# 09_ETHERNET_ENET.net
KiCad netlist of a schematic drawn in Altium Designer
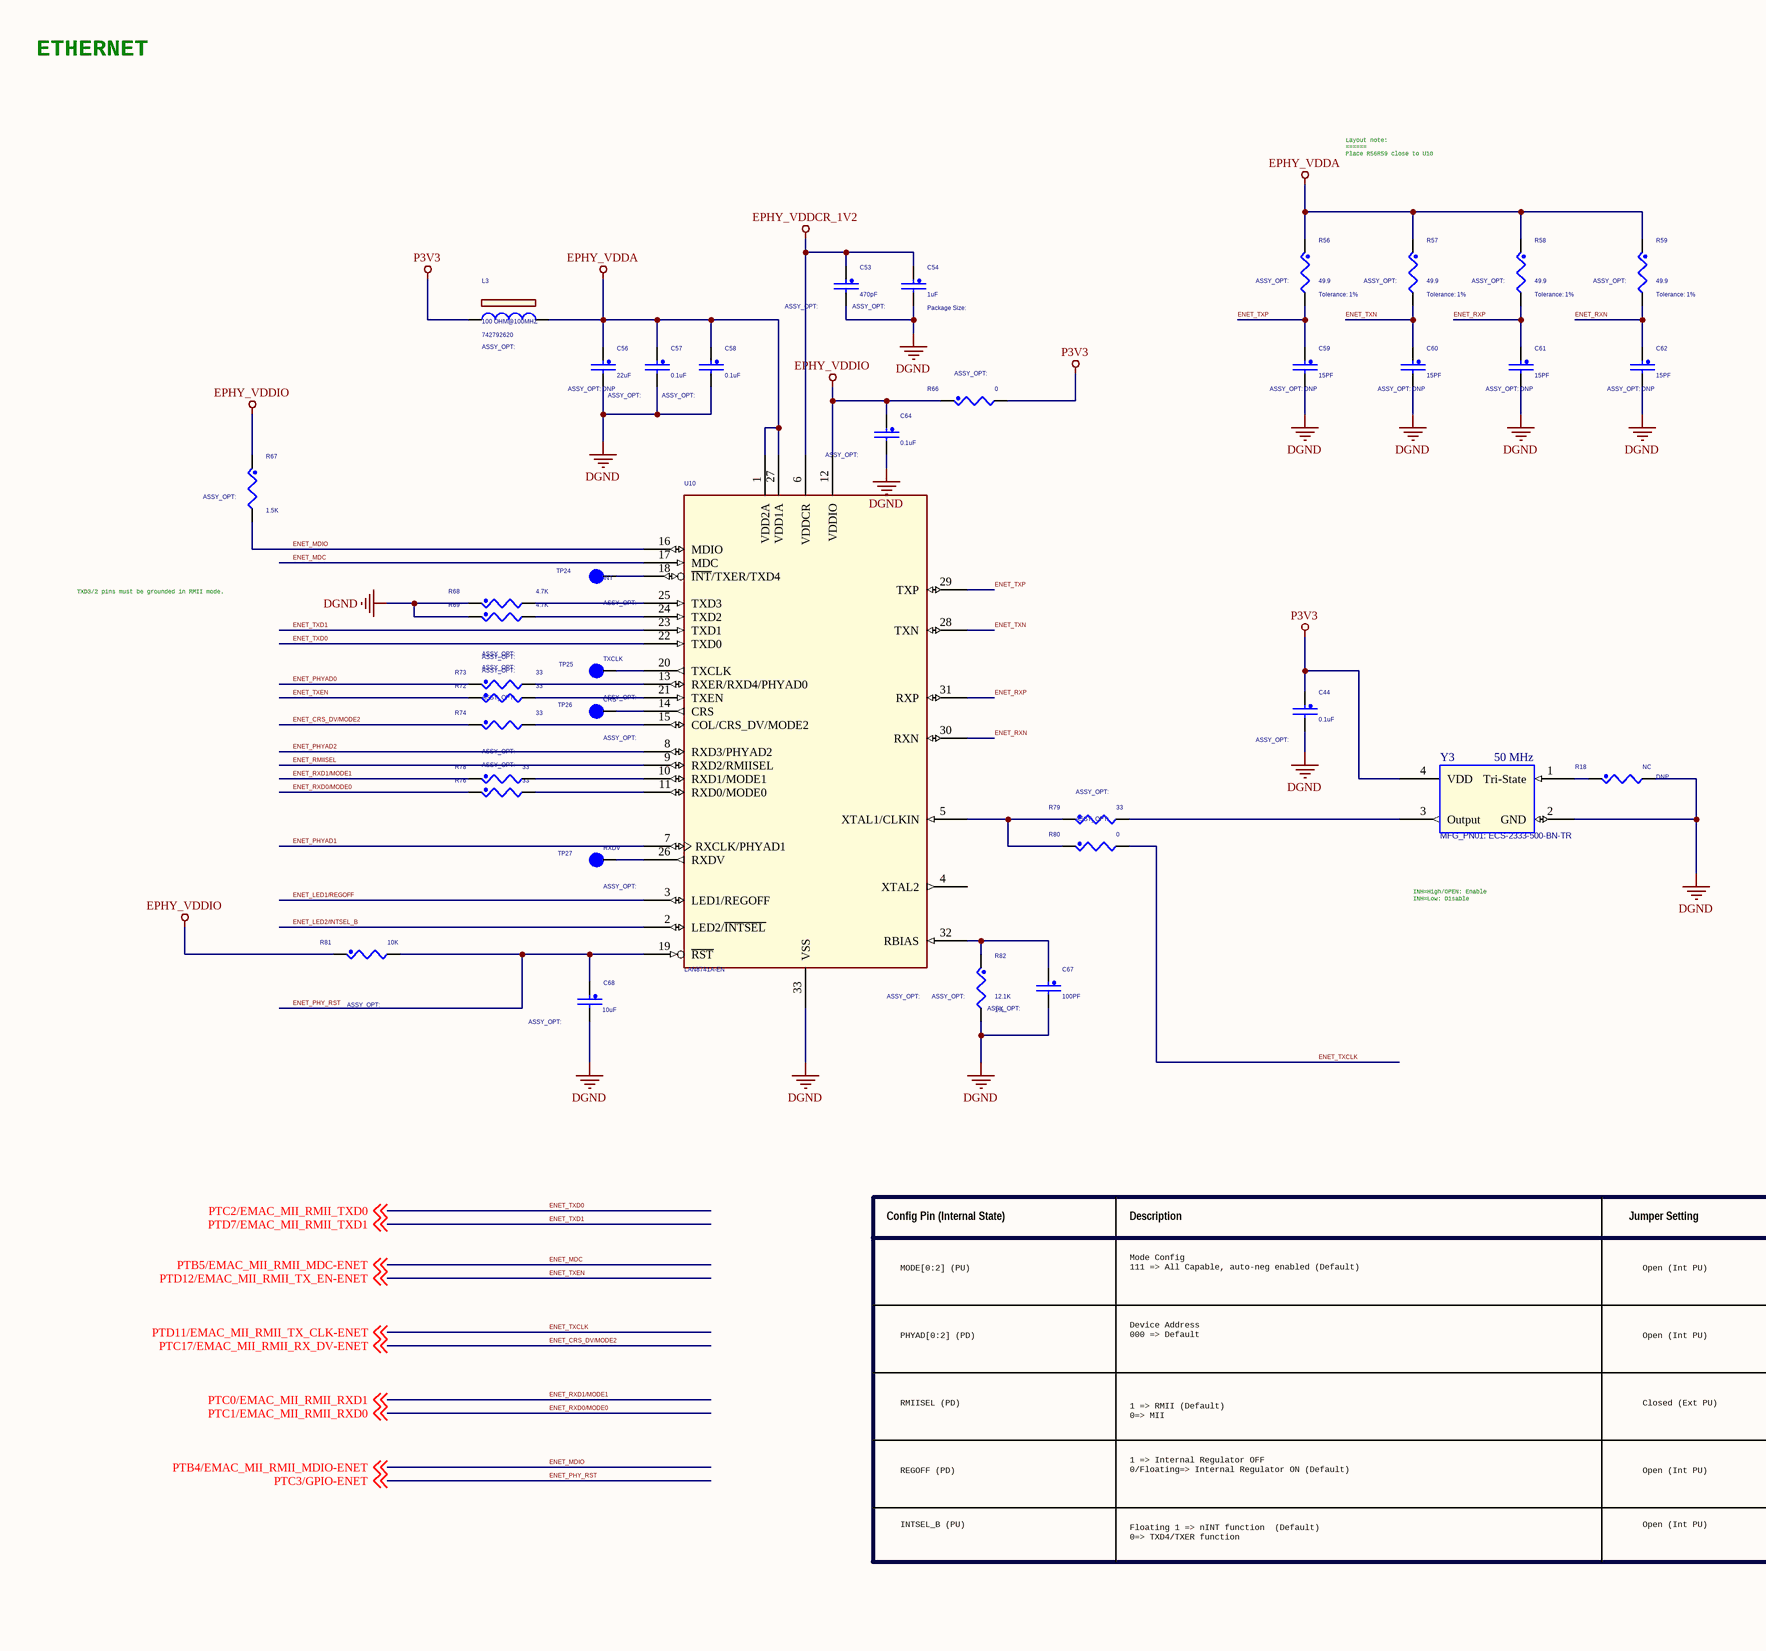
[diagram p0: 09 ETHERNET_ENET.SchDoc, left]
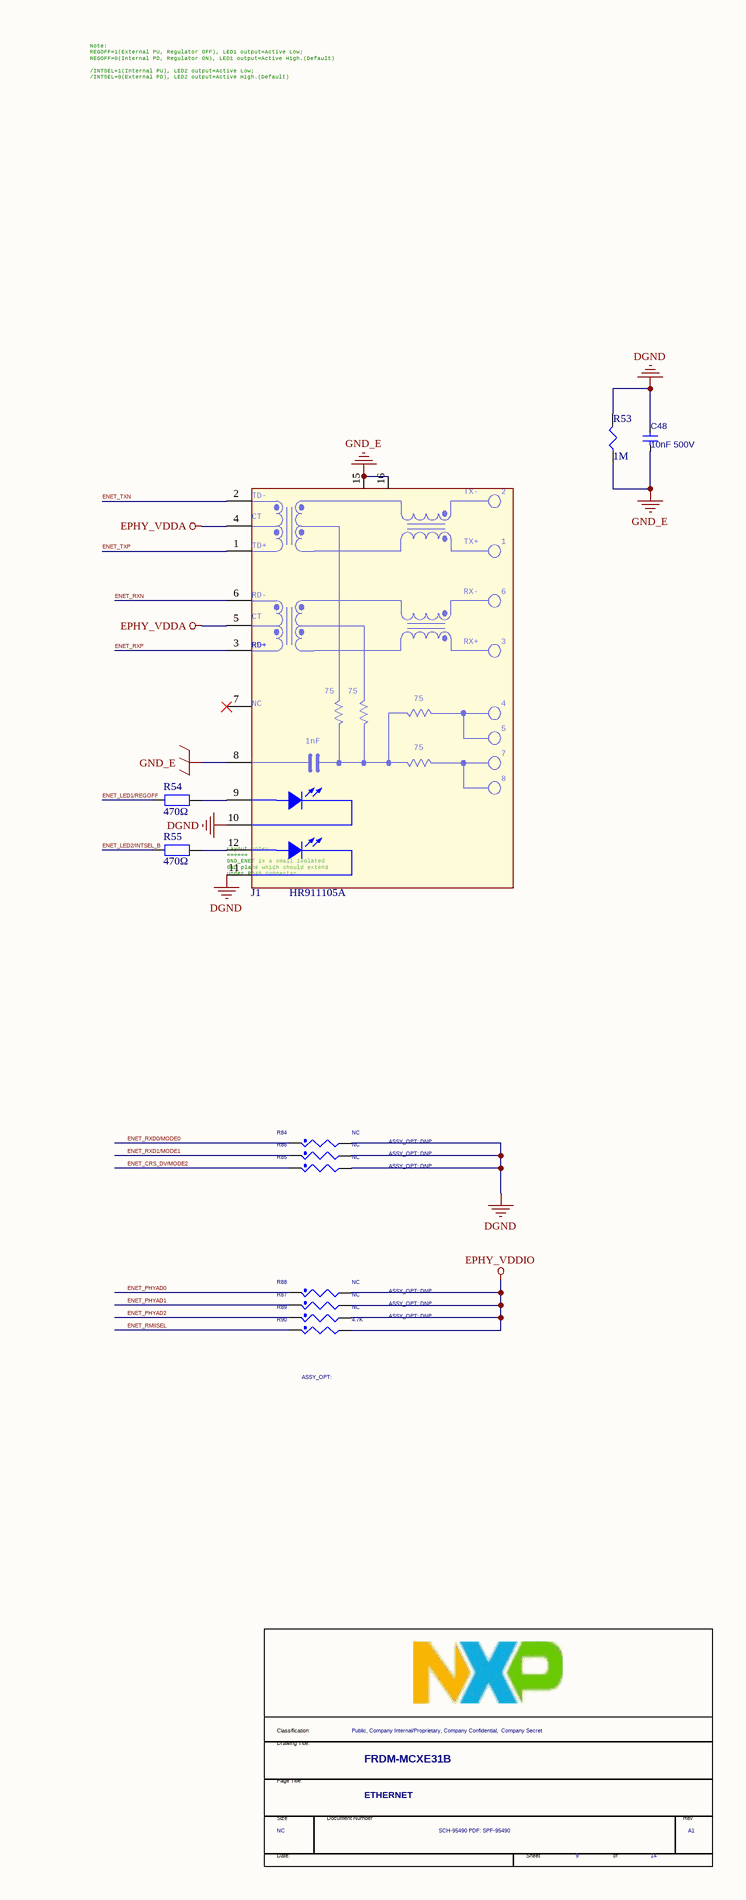
[diagram p1: 09 ETHERNET_ENET.SchDoc, right]

(export (version "E")
  (design (tool "Eeschema 10.0.6"))
  (components
    (comp (ref "C44")
      (value "0.1uF")
      (footprint "CC0402_25")
      (description "CAP CER 0.1UF 16V 10% X7R 0402")
      (fields (field (name "TOLERANCE") "10%") (field (name "VOLTAGE") "16V"))
      (libsource (lib "*") (part "CAP_NP"))
    )
    (comp (ref "C48") (value "10nF 500V") (footprint "1210") (libsource (lib "*") (part "CAP")))
    (comp (ref "C53")
      (value "470pF")
      (footprint "CC0402_25")
      (description "CAP CER 470pF 50V 5% C0G 0402")
      (fields (field (name "TOLERANCE") "5%"))
      (libsource (lib "*") (part "CAP_NP"))
    )
    (comp (ref "C54")
      (value "1uF")
      (footprint "CC0402_25")
      (description "CAP CER 1.0uF 16V 10% X6S 0402")
      (fields (field (name "VOLTAGE") "16V") (field (name "TOLERANCE") "10%"))
      (libsource (lib "*") (part "CAP_NP"))
    )
    (comp (ref "C56")
      (value "22uF")
      (footprint "CC0603_OV")
      (description "CAP CER 22uF 10V 20% X5R 0603")
      (fields (field (name "ASSY_OPT") "DNP") (field (name "TOLERANCE") "20%"))
      (libsource (lib "*") (part "CAP_NP"))
    )
    (comp (ref "C57")
      (value "0.1uF")
      (footprint "CC0402_25")
      (description "CAP CER 0.1UF 16V 10% X7R 0402")
      (fields (field (name "TOLERANCE") "10%") (field (name "VOLTAGE") "16V"))
      (libsource (lib "*") (part "CAP_NP"))
    )
    (comp (ref "C58")
      (value "0.1uF")
      (footprint "CC0402_25")
      (description "CAP CER 0.1UF 16V 10% X7R 0402")
      (fields (field (name "TOLERANCE") "10%") (field (name "VOLTAGE") "16V"))
      (libsource (lib "*") (part "CAP_NP"))
    )
    (comp (ref "C59")
      (value "15PF")
      (footprint "CC0402_25")
      (description "CAP CER 15pF 50V 5% C0G 0402")
      (fields (field (name "ASSY_OPT") "DNP") (field (name "TOLERANCE") "5%"))
      (libsource (lib "*") (part "CAP_NP"))
    )
    (comp (ref "C60")
      (value "15PF")
      (footprint "CC0402_25")
      (description "CAP CER 15pF 50V 5% C0G 0402")
      (fields (field (name "ASSY_OPT") "DNP") (field (name "TOLERANCE") "5%"))
      (libsource (lib "*") (part "CAP_NP"))
    )
    (comp (ref "C61")
      (value "15PF")
      (footprint "CC0402_25")
      (description "CAP CER 15pF 50V 5% C0G 0402")
      (fields (field (name "ASSY_OPT") "DNP") (field (name "TOLERANCE") "5%"))
      (libsource (lib "*") (part "CAP_NP"))
    )
    (comp (ref "C62")
      (value "15PF")
      (footprint "CC0402_25")
      (description "CAP CER 15pF 50V 5% C0G 0402")
      (fields (field (name "ASSY_OPT") "DNP") (field (name "TOLERANCE") "5%"))
      (libsource (lib "*") (part "CAP_NP"))
    )
    (comp (ref "C64")
      (value "0.1uF")
      (footprint "CC0402_25")
      (description "CAP CER 0.1UF 16V 10% X7R 0402")
      (fields (field (name "TOLERANCE") "10%") (field (name "VOLTAGE") "16V"))
      (libsource (lib "*") (part "CAP_NP"))
    )
    (comp (ref "C67")
      (value "100PF")
      (footprint "CC0402_25")
      (description "CAP CER 100pF 16V 10% X7R 0402")
      (fields (field (name "TOLERANCE") "10%"))
      (libsource (lib "*") (part "CAP_NP"))
    )
    (comp (ref "C68")
      (value "10uF")
      (footprint "CC0402_25")
      (description "CAP CER 10uF 25V 20% X5R 0603")
      (fields (field (name "TOLERANCE") "20%"))
      (libsource (lib "*") (part "CAP_NP"))
    )
    (comp (ref "J1")
      (value "HR911105A")
      (footprint "RJ45-HR911105A")
      (libsource (lib "GatewaySchlib_V2") (part "HR911105A"))
    )
    (comp (ref "L3")
      (value "100 OHM@100MHZ")
      (footprint "L 0603_L")
      (description "IND FER BEAD 100 OHM@100MHz 0.5A 25% AEC-Q200 0603")
      (fields (field (name "MFG_PN01") "742792620"))
      (libsource (lib "*") (part "INDUCTOR_FERRITE"))
    )
    (comp (ref "R18")
      (value "NC")
      (footprint "RC0402_25")
      (description "RES MF ZERO OHM 1/10W -- 0603")
      (fields (field (name "ASSY_OPT") "DNP"))
      (libsource (lib "*") (part "RES"))
    )
    (comp (ref "R53") (value "1M") (footprint "1210") (libsource (lib "armdesign_schlib1") (part "R")))
    (comp (ref "R54")
      (value "470Ω")
      (footprint "R0603")
      (description "贴片电阻")
      (fields (field (name "版权归属") "源创客"))
      (libsource (lib "PCB_Project_1") (part "R"))
    )
    (comp (ref "R55")
      (value "470Ω")
      (footprint "R0603")
      (description "贴片电阻")
      (fields (field (name "版权归属") "源创客"))
      (libsource (lib "PCB_Project_1") (part "R"))
    )
    (comp (ref "R56")
      (value "49.9")
      (footprint "RC0402_25")
      (description "RES MF 49.9 OHM 1/16W 1% 0402")
      (fields (field (name "TOLERANCE") "1%"))
      (libsource (lib "*") (part "RES"))
    )
    (comp (ref "R57")
      (value "49.9")
      (footprint "RC0402_25")
      (description "RES MF 49.9 OHM 1/16W 1% 0402")
      (fields (field (name "TOLERANCE") "1%"))
      (libsource (lib "*") (part "RES"))
    )
    (comp (ref "R58")
      (value "49.9")
      (footprint "RC0402_25")
      (description "RES MF 49.9 OHM 1/16W 1% 0402")
      (fields (field (name "TOLERANCE") "1%"))
      (libsource (lib "*") (part "RES"))
    )
    (comp (ref "R59")
      (value "49.9")
      (footprint "RC0402_25")
      (description "RES MF 49.9 OHM 1/16W 1% 0402")
      (fields (field (name "TOLERANCE") "1%"))
      (libsource (lib "*") (part "RES"))
    )
    (comp (ref "R66")
      (value "0")
      (footprint "RC0603_OV")
      (description "RES MF ZERO OHM 1/10W -- 0603")
      (libsource (lib "*") (part "RES"))
    )
    (comp (ref "R67")
      (value "1.5K")
      (footprint "RC0402_25")
      (description "RES MF 1.5K 1/16W 1% 0402")
      (fields (field (name "TOLERANCE") "1%"))
      (libsource (lib "*") (part "RES"))
    )
    (comp (ref "R68")
      (value "4.7K")
      (footprint "RC0402_25")
      (description "RES MF 4.7K 1/16W 5% 0402")
      (fields (field (name "TOLERANCE") "5%"))
      (libsource (lib "*") (part "RES"))
    )
    (comp (ref "R69")
      (value "4.7K")
      (footprint "RC0402_25")
      (description "RES MF 4.7K 1/16W 5% 0402")
      (fields (field (name "TOLERANCE") "5%"))
      (libsource (lib "*") (part "RES"))
    )
    (comp (ref "R72")
      (value "33")
      (footprint "RC0402_25")
      (description "RES MF 33.0 OHM 1/16W 1% 0402")
      (fields (field (name "TOLERANCE") "1%"))
      (libsource (lib "*") (part "RES"))
    )
    (comp (ref "R73")
      (value "33")
      (footprint "RC0402_25")
      (description "RES MF 33.0 OHM 1/16W 1% 0402")
      (fields (field (name "TOLERANCE") "1%"))
      (libsource (lib "*") (part "RES"))
    )
    (comp (ref "R74")
      (value "33")
      (footprint "RC0402_25")
      (description "RES MF 33.0 OHM 1/16W 1% 0402")
      (fields (field (name "TOLERANCE") "1%"))
      (libsource (lib "*") (part "RES"))
    )
    (comp (ref "R76")
      (value "33")
      (footprint "RC0402_25")
      (description "RES MF 33.0 OHM 1/16W 1% 0402")
      (fields (field (name "TOLERANCE") "1%"))
      (libsource (lib "*") (part "RES"))
    )
    (comp (ref "R78")
      (value "33")
      (footprint "RC0402_25")
      (description "RES MF 33.0 OHM 1/16W 1% 0402")
      (fields (field (name "TOLERANCE") "1%"))
      (libsource (lib "*") (part "RES"))
    )
    (comp (ref "R79")
      (value "33")
      (footprint "RC0402_25")
      (description "RES MF 33.0 OHM 1/16W 1% 0402")
      (fields (field (name "TOLERANCE") "1%"))
      (libsource (lib "*") (part "RES"))
    )
    (comp (ref "R80")
      (value "0")
      (footprint "RC0402_25")
      (description "RES MF ZERO OHM 1/10W -- 0603")
      (libsource (lib "*") (part "RES"))
    )
    (comp (ref "R81")
      (value "10K")
      (footprint "RC0402_25")
      (description "RES MF 10K 1/16W 5% 0402")
      (fields (field (name "TOLERANCE") "5%"))
      (libsource (lib "*") (part "RES"))
    )
    (comp (ref "R82")
      (value "12.1K")
      (footprint "RC0402_25")
      (description "RES MF 12.1K 1/16W 1% 0402")
      (fields (field (name "TOLERANCE") "1%"))
      (libsource (lib "*") (part "RES"))
    )
    (comp (ref "R84")
      (value "NC")
      (footprint "RC0402_25")
      (description "RES MF 4.7K 1/16W 5% 0402")
      (fields (field (name "ASSY_OPT") "DNP") (field (name "TOLERANCE") "5%"))
      (libsource (lib "*") (part "RES"))
    )
    (comp (ref "R85")
      (value "NC")
      (footprint "RC0402_25")
      (description "RES MF 4.7K 1/16W 5% 0402")
      (fields (field (name "ASSY_OPT") "DNP") (field (name "TOLERANCE") "5%"))
      (libsource (lib "*") (part "RES"))
    )
    (comp (ref "R86")
      (value "NC")
      (footprint "RC0402_25")
      (description "RES MF 4.7K 1/16W 5% 0402")
      (fields (field (name "ASSY_OPT") "DNP") (field (name "TOLERANCE") "5%"))
      (libsource (lib "*") (part "RES"))
    )
    (comp (ref "R87")
      (value "NC")
      (footprint "RC0402_25")
      (description "RES MF 4.7K 1/16W 5% 0402")
      (fields (field (name "ASSY_OPT") "DNP") (field (name "TOLERANCE") "5%"))
      (libsource (lib "*") (part "RES"))
    )
    (comp (ref "R88")
      (value "NC")
      (footprint "RC0402_25")
      (description "RES MF 4.7K 1/16W 5% 0402")
      (fields (field (name "ASSY_OPT") "DNP") (field (name "TOLERANCE") "5%"))
      (libsource (lib "*") (part "RES"))
    )
    (comp (ref "R89")
      (value "NC")
      (footprint "RC0402_25")
      (description "RES MF 4.7K 1/16W 5% 0402")
      (fields (field (name "ASSY_OPT") "DNP") (field (name "TOLERANCE") "5%"))
      (libsource (lib "*") (part "RES"))
    )
    (comp (ref "R90")
      (value "4.7K")
      (footprint "RC0402_25")
      (description "RES MF 4.7K 1/16W 5% 0402")
      (fields (field (name "TOLERANCE") "5%"))
      (libsource (lib "*") (part "RES"))
    )
    (comp (ref "TP24")
      (value "TPAD_030")
      (footprint "TPAD_030")
      (description "TEST POINT PAD 30MIL DIA SMT, NO PART TO ORDER")
      (fields (field (name "SILK") "INT"))
      (libsource (lib "*") (part "TESTLOOP"))
    )
    (comp (ref "TP25")
      (value "TPAD_030")
      (footprint "TPAD_030")
      (description "TEST POINT PAD 30MIL DIA SMT, NO PART TO ORDER")
      (fields (field (name "SILK") "TXCLK"))
      (libsource (lib "*") (part "TESTLOOP"))
    )
    (comp (ref "TP26")
      (value "TPAD_030")
      (footprint "TPAD_030")
      (description "TEST POINT PAD 30MIL DIA SMT, NO PART TO ORDER")
      (fields (field (name "SILK") "CRS"))
      (libsource (lib "*") (part "TESTLOOP"))
    )
    (comp (ref "TP27")
      (value "TPAD_030")
      (footprint "TPAD_030")
      (description "TEST POINT PAD 30MIL DIA SMT, NO PART TO ORDER")
      (fields (field (name "SILK") "RXDV"))
      (libsource (lib "*") (part "TESTLOOP"))
    )
    (comp (ref "U10")
      (value "LAN8741A-EN")
      (footprint "QFN-32-EP(5x5)")
      (description "IC XCVR ETHERNET PHY MII/RMII 1.8-3.3V SQFN32")
      (fields (field (name "MFG_PN01") "LAN8741A-EN"))
      (libsource (lib "*") (part "LAN8710"))
    )
    (comp (ref "Y3")
      (value "50 MHz")
      (footprint "OSC-SMD_4P-L3.2-W2.5-BL")
      (description "OSC XO 50MHZ 3.3V SMD")
      (fields (field (name "MFG_PN01") "ECS-2333-500-BN-TR"))
      (libsource (lib "PCB_Project") (part "OSC_ASFL"))
    )
  )
  (nets
    (net (code "1") (name "/ENET_LED1{slash}REGOFF") (class "Default")
      (node (ref "R54") (pin "2") (pinfunction "2_2") (pintype "passive"))
      (node (ref "U10") (pin "3") (pinfunction "LED1/REGOFF_3") (pintype "bidirectional"))
    )
    (net (code "2") (name "/ENET_LED2{slash}INTSEL_B") (class "Default")
      (node (ref "R55") (pin "2") (pinfunction "2_2") (pintype "passive"))
      (node (ref "U10") (pin "2") (pinfunction "LED2/~{INTSEL}_2") (pintype "bidirectional"))
    )
    (net (code "3") (name "/ENET_PHYAD0") (class "Default")
      (node (ref "R73") (pin "1") (pinfunction "1_1") (pintype "passive"))
      (node (ref "R88") (pin "1") (pinfunction "1_1") (pintype "passive"))
    )
    (net (code "4") (name "/ENET_PHYAD1") (class "Default")
      (node (ref "R87") (pin "1") (pinfunction "1_1") (pintype "passive"))
      (node (ref "U10") (pin "7") (pinfunction "RXCLK/PHYAD1_7") (pintype "bidirectional"))
    )
    (net (code "5") (name "/ENET_PHYAD2") (class "Default")
      (node (ref "R89") (pin "1") (pinfunction "1_1") (pintype "passive"))
      (node (ref "U10") (pin "8") (pinfunction "RXD3/PHYAD2_8") (pintype "bidirectional"))
    )
    (net (code "6") (name "/ENET_RMIISEL") (class "Default")
      (node (ref "R90") (pin "1") (pinfunction "1_1") (pintype "passive"))
      (node (ref "U10") (pin "9") (pinfunction "RXD2/RMIISEL_9") (pintype "bidirectional"))
    )
    (net (code "7") (name "/ENET_RXN") (class "Default")
      (node (ref "C62") (pin "1") (pinfunction "1_1") (pintype "passive"))
      (node (ref "J1") (pin "6") (pinfunction "P6_6") (pintype "passive"))
      (node (ref "R59") (pin "2") (pinfunction "2_2") (pintype "passive"))
      (node (ref "U10") (pin "30") (pinfunction "RXN_30") (pintype "bidirectional"))
    )
    (net (code "8") (name "/ENET_RXP") (class "Default")
      (node (ref "C61") (pin "1") (pinfunction "1_1") (pintype "passive"))
      (node (ref "J1") (pin "3") (pinfunction "P3_3") (pintype "passive"))
      (node (ref "R58") (pin "2") (pinfunction "2_2") (pintype "passive"))
      (node (ref "U10") (pin "31") (pinfunction "RXP_31") (pintype "bidirectional"))
    )
    (net (code "9") (name "/ENET_TXN") (class "Default")
      (node (ref "C60") (pin "1") (pinfunction "1_1") (pintype "passive"))
      (node (ref "J1") (pin "2") (pinfunction "P2_2") (pintype "passive"))
      (node (ref "R57") (pin "2") (pinfunction "2_2") (pintype "passive"))
      (node (ref "U10") (pin "28") (pinfunction "TXN_28") (pintype "bidirectional"))
    )
    (net (code "10") (name "/ENET_TXP") (class "Default")
      (node (ref "C59") (pin "1") (pinfunction "1_1") (pintype "passive"))
      (node (ref "J1") (pin "1") (pinfunction "P1_1") (pintype "passive"))
      (node (ref "R56") (pin "2") (pinfunction "2_2") (pintype "passive"))
      (node (ref "U10") (pin "29") (pinfunction "TXP_29") (pintype "bidirectional"))
    )
    (net (code "11") (name "DGND") (class "Default")
      (node (ref "C44") (pin "2") (pinfunction "2_2") (pintype "passive"))
      (node (ref "C48") (pin "2") (pintype "passive"))
      (node (ref "C53") (pin "2") (pinfunction "2_2") (pintype "passive"))
      (node (ref "C54") (pin "2") (pinfunction "2_2") (pintype "passive"))
      (node (ref "C56") (pin "2") (pinfunction "2_2") (pintype "passive"))
      (node (ref "C57") (pin "2") (pinfunction "2_2") (pintype "passive"))
      (node (ref "C58") (pin "2") (pinfunction "2_2") (pintype "passive"))
      (node (ref "C59") (pin "2") (pinfunction "2_2") (pintype "passive"))
      (node (ref "C60") (pin "2") (pinfunction "2_2") (pintype "passive"))
      (node (ref "C61") (pin "2") (pinfunction "2_2") (pintype "passive"))
      (node (ref "C62") (pin "2") (pinfunction "2_2") (pintype "passive"))
      (node (ref "C64") (pin "2") (pinfunction "2_2") (pintype "passive"))
      (node (ref "C67") (pin "2") (pinfunction "2_2") (pintype "passive"))
      (node (ref "C68") (pin "2") (pinfunction "2_2") (pintype "passive"))
      (node (ref "J1") (pin "10") (pinfunction "CATHODE_10") (pintype "passive"))
      (node (ref "J1") (pin "11") (pinfunction "CATHODE_11") (pintype "passive"))
      (node (ref "R18") (pin "2") (pinfunction "2_2") (pintype "passive"))
      (node (ref "R53") (pin "2") (pinfunction "2_2") (pintype "passive"))
      (node (ref "R68") (pin "1") (pinfunction "1_1") (pintype "passive"))
      (node (ref "R69") (pin "1") (pinfunction "1_1") (pintype "passive"))
      (node (ref "R82") (pin "2") (pinfunction "2_2") (pintype "passive"))
      (node (ref "R84") (pin "2") (pinfunction "2_2") (pintype "passive"))
      (node (ref "R85") (pin "2") (pinfunction "2_2") (pintype "passive"))
      (node (ref "R86") (pin "2") (pinfunction "2_2") (pintype "passive"))
      (node (ref "U10") (pin "33") (pinfunction "VSS_33") (pintype "power_in"))
      (node (ref "Y3") (pin "2") (pinfunction "GND_2") (pintype "bidirectional"))
    )
    (net (code "12") (name "EPHY_VDDA") (class "Default")
      (node (ref "C56") (pin "1") (pinfunction "1_1") (pintype "passive"))
      (node (ref "C57") (pin "1") (pinfunction "1_1") (pintype "passive"))
      (node (ref "C58") (pin "1") (pinfunction "1_1") (pintype "passive"))
      (node (ref "J1") (pin "4") (pinfunction "P4_4") (pintype "passive"))
      (node (ref "J1") (pin "5") (pinfunction "P5_5") (pintype "passive"))
      (node (ref "L3") (pin "2") (pinfunction "2_2") (pintype "passive"))
      (node (ref "R56") (pin "1") (pinfunction "1_1") (pintype "passive"))
      (node (ref "R57") (pin "1") (pinfunction "1_1") (pintype "passive"))
      (node (ref "R58") (pin "1") (pinfunction "1_1") (pintype "passive"))
      (node (ref "R59") (pin "1") (pinfunction "1_1") (pintype "passive"))
      (node (ref "U10") (pin "1") (pinfunction "VDD2A_1") (pintype "power_in"))
      (node (ref "U10") (pin "27") (pinfunction "VDD1A_27") (pintype "power_in"))
    )
    (net (code "13") (name "EPHY_VDDCR_1V2") (class "Default")
      (node (ref "C53") (pin "1") (pinfunction "1_1") (pintype "passive"))
      (node (ref "C54") (pin "1") (pinfunction "1_1") (pintype "passive"))
      (node (ref "U10") (pin "6") (pinfunction "VDDCR_6") (pintype "power_in"))
    )
    (net (code "14") (name "EPHY_VDDIO") (class "Default")
      (node (ref "C64") (pin "1") (pinfunction "1_1") (pintype "passive"))
      (node (ref "R66") (pin "1") (pinfunction "1_1") (pintype "passive"))
      (node (ref "R67") (pin "1") (pinfunction "1_1") (pintype "passive"))
      (node (ref "R81") (pin "1") (pinfunction "1_1") (pintype "passive"))
      (node (ref "R87") (pin "2") (pinfunction "2_2") (pintype "passive"))
      (node (ref "R88") (pin "2") (pinfunction "2_2") (pintype "passive"))
      (node (ref "R89") (pin "2") (pinfunction "2_2") (pintype "passive"))
      (node (ref "R90") (pin "2") (pinfunction "2_2") (pintype "passive"))
      (node (ref "U10") (pin "12") (pinfunction "VDDIO_12") (pintype "power_in"))
    )
    (net (code "15") (name "GND_E") (class "Default")
      (node (ref "C48") (pin "1") (pintype "passive"))
      (node (ref "J1") (pin "15") (pinfunction "P15_15") (pintype "passive"))
      (node (ref "J1") (pin "16") (pinfunction "P16_16") (pintype "passive"))
      (node (ref "J1") (pin "8") (pinfunction "P8_8") (pintype "passive"))
      (node (ref "R53") (pin "1") (pinfunction "1_1") (pintype "passive"))
    )
    (net (code "16") (name "Net-(J1-ANODE-Pad9)") (class "Default")
      (node (ref "J1") (pin "9") (pinfunction "ANODE_9") (pintype "passive"))
      (node (ref "R54") (pin "1") (pinfunction "1_1") (pintype "passive"))
    )
    (net (code "17") (name "Net-(J1-ANODE-Pad12)") (class "Default")
      (node (ref "J1") (pin "12") (pinfunction "ANODE_12") (pintype "passive"))
      (node (ref "R55") (pin "1") (pinfunction "1_1") (pintype "passive"))
    )
    (net (code "18") (name "Net-(TP24-Pin1)") (class "Default")
      (node (ref "TP24") (pin "1") (pinfunction "Pin1_1") (pintype "passive"))
      (node (ref "U10") (pin "18") (pinfunction "~{INT}/TXER/TXD4_18") (pintype "bidirectional"))
    )
    (net (code "19") (name "Net-(TP25-Pin1)") (class "Default")
      (node (ref "TP25") (pin "1") (pinfunction "Pin1_1") (pintype "passive"))
      (node (ref "U10") (pin "20") (pinfunction "TXCLK_20") (pintype "output"))
    )
    (net (code "20") (name "Net-(TP26-Pin1)") (class "Default")
      (node (ref "TP26") (pin "1") (pinfunction "Pin1_1") (pintype "passive"))
      (node (ref "U10") (pin "14") (pinfunction "CRS_14") (pintype "output"))
    )
    (net (code "21") (name "Net-(TP27-Pin1)") (class "Default")
      (node (ref "TP27") (pin "1") (pinfunction "Pin1_1") (pintype "passive"))
      (node (ref "U10") (pin "26") (pinfunction "RXDV_26") (pintype "output"))
    )
    (net (code "22") (name "Net-(U10-COL{slash}CRS_DV{slash}MODE2)") (class "Default")
      (node (ref "R74") (pin "2") (pinfunction "2_2") (pintype "passive"))
      (node (ref "U10") (pin "15") (pinfunction "COL/CRS_DV/MODE2_15") (pintype "bidirectional"))
    )
    (net (code "23") (name "Net-(U10-RBIAS)") (class "Default")
      (node (ref "C67") (pin "1") (pinfunction "1_1") (pintype "passive"))
      (node (ref "R82") (pin "1") (pinfunction "1_1") (pintype "passive"))
      (node (ref "U10") (pin "32") (pinfunction "RBIAS_32") (pintype "input"))
    )
    (net (code "24") (name "Net-(U10-RXD0{slash}MODE0)") (class "Default")
      (node (ref "R76") (pin "2") (pinfunction "2_2") (pintype "passive"))
      (node (ref "U10") (pin "11") (pinfunction "RXD0/MODE0_11") (pintype "bidirectional"))
    )
    (net (code "25") (name "Net-(U10-RXD1{slash}MODE1)") (class "Default")
      (node (ref "R78") (pin "2") (pinfunction "2_2") (pintype "passive"))
      (node (ref "U10") (pin "10") (pinfunction "RXD1/MODE1_10") (pintype "bidirectional"))
    )
    (net (code "26") (name "Net-(U10-RXER{slash}RXD4{slash}PHYAD0)") (class "Default")
      (node (ref "R73") (pin "2") (pinfunction "2_2") (pintype "passive"))
      (node (ref "U10") (pin "13") (pinfunction "RXER/RXD4/PHYAD0_13") (pintype "bidirectional"))
    )
    (net (code "27") (name "Net-(U10-TXD2)") (class "Default")
      (node (ref "R69") (pin "2") (pinfunction "2_2") (pintype "passive"))
      (node (ref "U10") (pin "24") (pinfunction "TXD2_24") (pintype "input"))
    )
    (net (code "28") (name "Net-(U10-TXD3)") (class "Default")
      (node (ref "R68") (pin "2") (pinfunction "2_2") (pintype "passive"))
      (node (ref "U10") (pin "25") (pinfunction "TXD3_25") (pintype "input"))
    )
    (net (code "29") (name "Net-(U10-TXEN)") (class "Default")
      (node (ref "R72") (pin "2") (pinfunction "2_2") (pintype "passive"))
      (node (ref "U10") (pin "21") (pinfunction "TXEN_21") (pintype "input"))
    )
    (net (code "30") (name "Net-(U10-XTAL1{slash}CLKIN)") (class "Default")
      (node (ref "R79") (pin "1") (pinfunction "1_1") (pintype "passive"))
      (node (ref "R80") (pin "1") (pinfunction "1_1") (pintype "passive"))
      (node (ref "U10") (pin "5") (pinfunction "XTAL1/CLKIN_5") (pintype "input"))
    )
    (net (code "31") (name "Net-(Y3-Output)") (class "Default")
      (node (ref "R79") (pin "2") (pinfunction "2_2") (pintype "passive"))
      (node (ref "Y3") (pin "3") (pinfunction "Output_3") (pintype "output"))
    )
    (net (code "32") (name "Net-(Y3-Tri-State)") (class "Default")
      (node (ref "R18") (pin "1") (pinfunction "1_1") (pintype "passive"))
      (node (ref "Y3") (pin "1") (pinfunction "Tri-State_1") (pintype "input"))
    )
    (net (code "33") (name "P3V3") (class "Default")
      (node (ref "C44") (pin "1") (pinfunction "1_1") (pintype "passive"))
      (node (ref "L3") (pin "1") (pinfunction "1_1") (pintype "passive"))
      (node (ref "R66") (pin "2") (pinfunction "2_2") (pintype "passive"))
      (node (ref "Y3") (pin "4") (pinfunction "VDD_4") (pintype "power_in"))
    )
    (net (code "34") (name "PTB4{slash}EMAC_MII_RMII_MDIO-ENET") (class "Default")
      (node (ref "R67") (pin "2") (pinfunction "2_2") (pintype "passive"))
      (node (ref "U10") (pin "16") (pinfunction "MDIO_16") (pintype "bidirectional"))
    )
    (net (code "35") (name "PTB5{slash}EMAC_MII_RMII_MDC-ENET") (class "Default")
      (node (ref "U10") (pin "17") (pinfunction "MDC_17") (pintype "input"))
    )
    (net (code "36") (name "PTC0{slash}EMAC_MII_RMII_RXD1") (class "Default")
      (node (ref "R78") (pin "1") (pinfunction "1_1") (pintype "passive"))
      (node (ref "R86") (pin "1") (pinfunction "1_1") (pintype "passive"))
    )
    (net (code "37") (name "PTC1{slash}EMAC_MII_RMII_RXD0") (class "Default")
      (node (ref "R76") (pin "1") (pinfunction "1_1") (pintype "passive"))
      (node (ref "R84") (pin "1") (pinfunction "1_1") (pintype "passive"))
    )
    (net (code "38") (name "PTC2{slash}EMAC_MII_RMII_TXD0") (class "Default")
      (node (ref "U10") (pin "22") (pinfunction "TXD0_22") (pintype "input"))
    )
    (net (code "39") (name "PTC3{slash}GPIO-ENET") (class "Default")
      (node (ref "C68") (pin "1") (pinfunction "1_1") (pintype "passive"))
      (node (ref "R81") (pin "2") (pinfunction "2_2") (pintype "passive"))
      (node (ref "U10") (pin "19") (pinfunction "~{RST}_19") (pintype "input"))
    )
    (net (code "40") (name "PTC17{slash}EMAC_MII_RMII_RX_DV-ENET") (class "Default")
      (node (ref "R74") (pin "1") (pinfunction "1_1") (pintype "passive"))
      (node (ref "R85") (pin "1") (pinfunction "1_1") (pintype "passive"))
    )
    (net (code "41") (name "PTD7{slash}EMAC_MII_RMII_TXD1") (class "Default")
      (node (ref "U10") (pin "23") (pinfunction "TXD1_23") (pintype "input"))
    )
    (net (code "42") (name "PTD11{slash}EMAC_MII_RMII_TX_CLK-ENET") (class "Default")
      (node (ref "R80") (pin "2") (pinfunction "2_2") (pintype "passive"))
    )
    (net (code "43") (name "PTD12{slash}EMAC_MII_RMII_TX_EN-ENET") (class "Default")
      (node (ref "R72") (pin "1") (pinfunction "1_1") (pintype "passive"))
    )
    (net (code "44") (name "unconnected-(J1-P7-Pad7)") (class "Default")
      (node (ref "J1") (pin "7") (pinfunction "P7_7") (pintype "passive+no_connect"))
    )
    (net (code "45") (name "unconnected-(U10-XTAL2-Pad4)") (class "Default")
      (node (ref "U10") (pin "4") (pinfunction "XTAL2_4") (pintype "output"))
    )
  )
)
